# eib-64_center.net
KiCad netlist of a schematic drawn in EAGLE
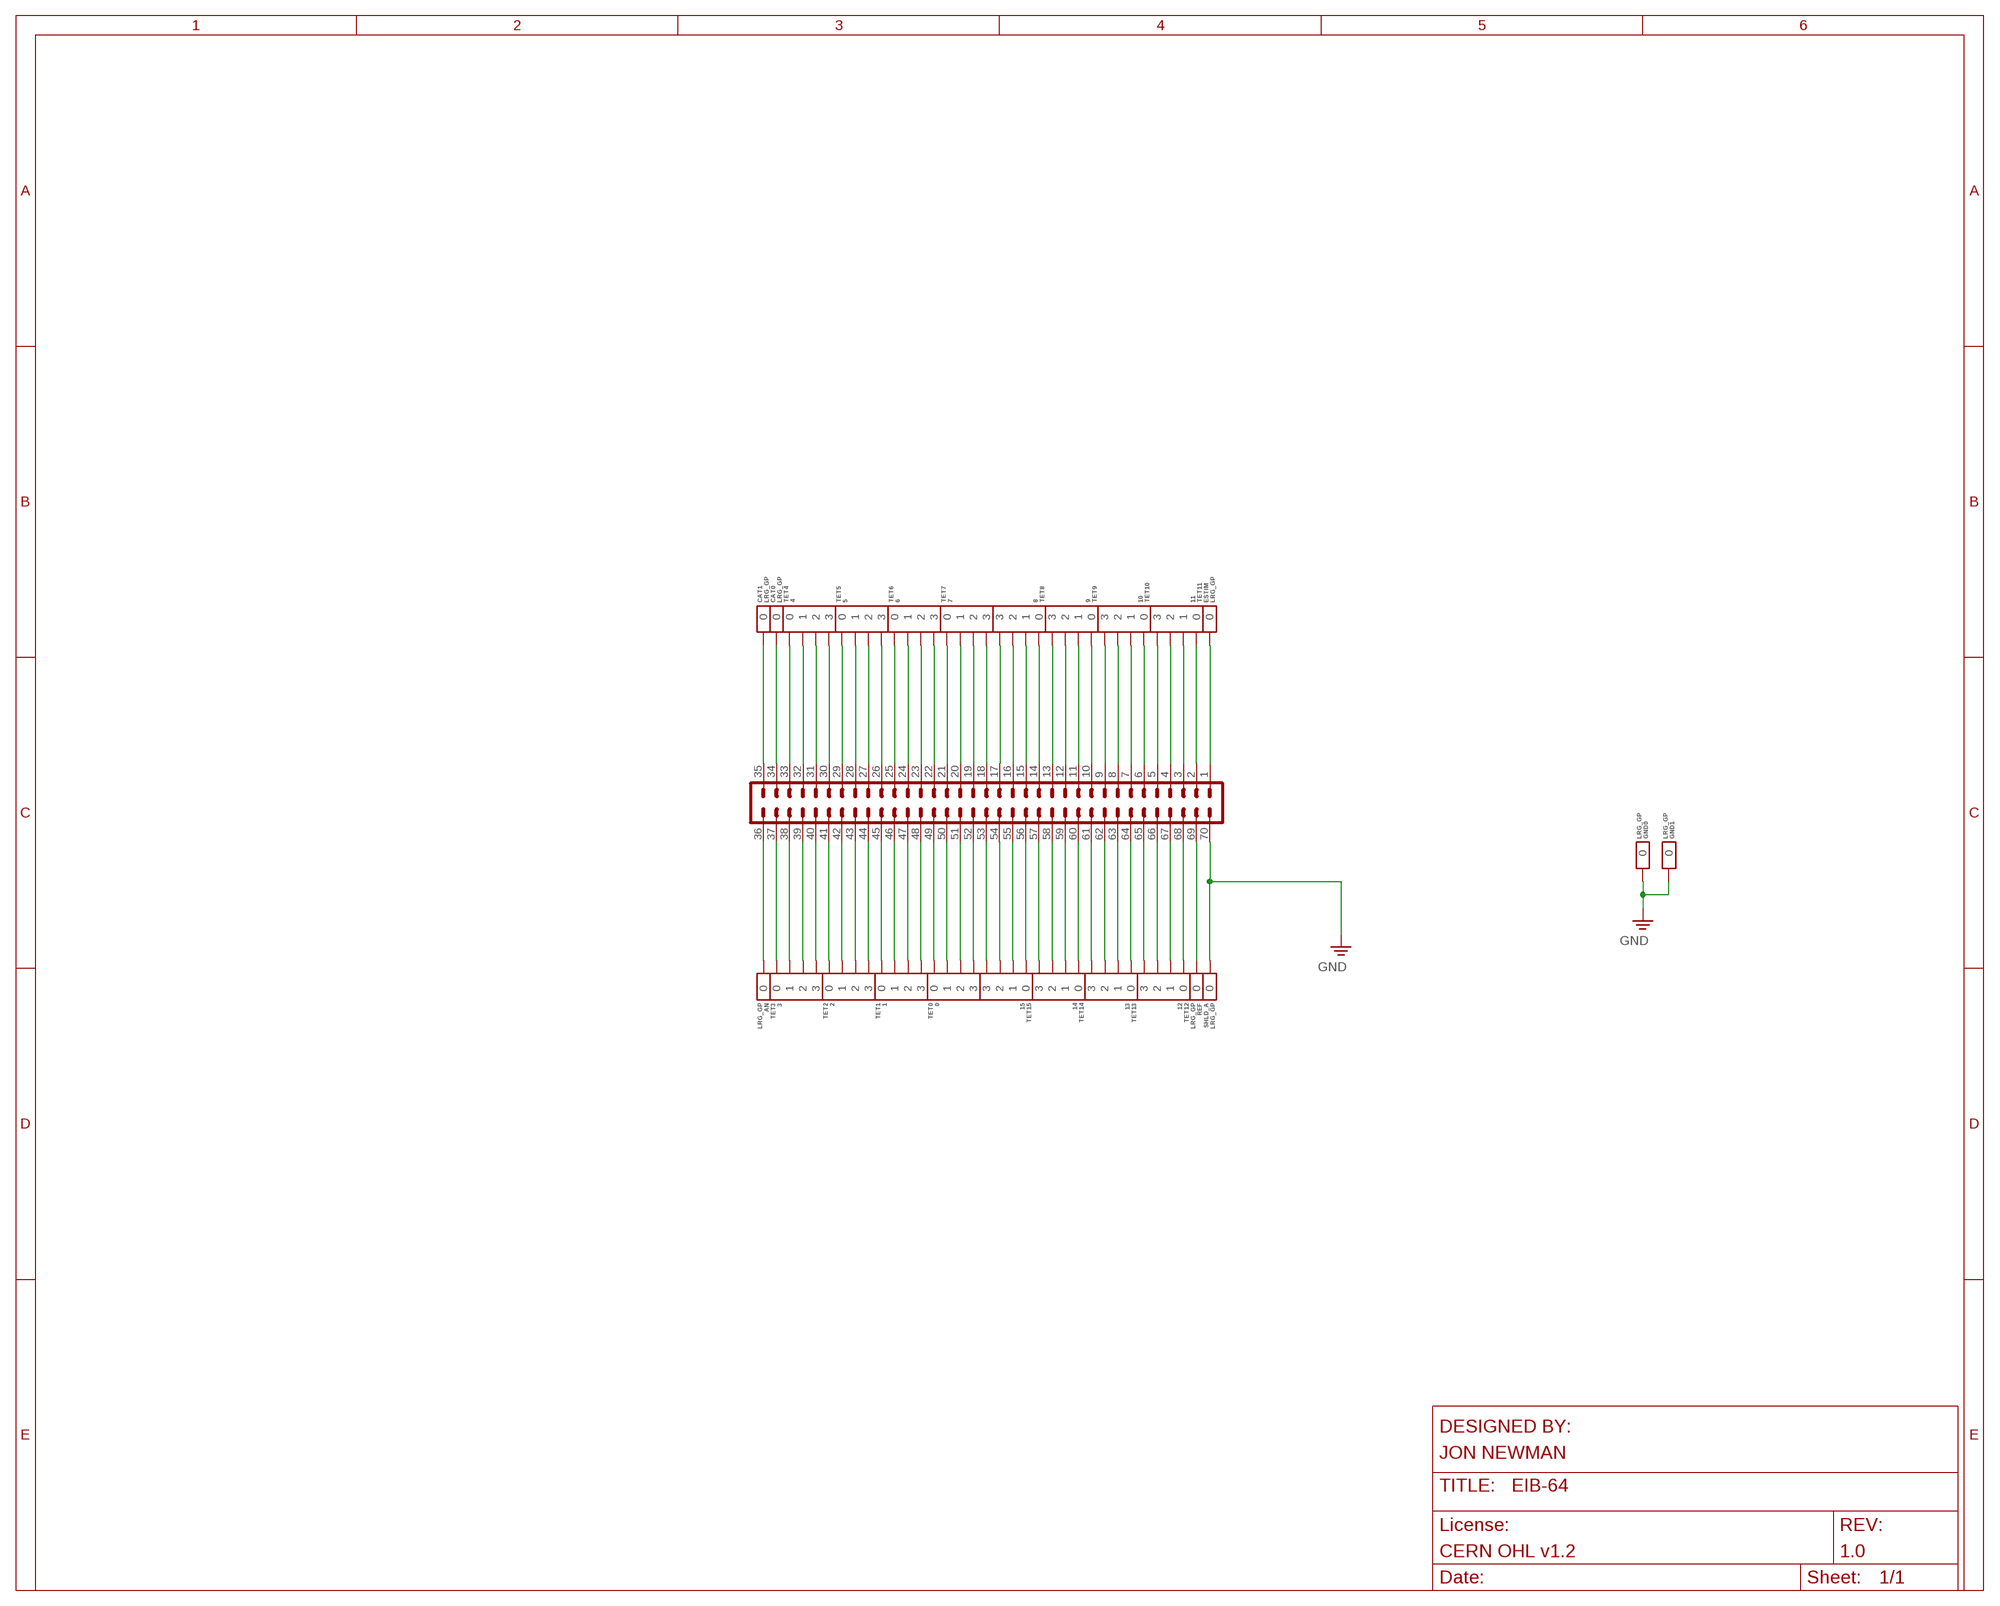
[diagram p0: schematic, sheet 1]

(export (version "E")
  (design (tool "Eeschema 10.0.6"))
  (components
    (comp (ref "AN")
      (value "LRG_GP")
      (footprint "eagle-import:GOLDPIN_0.5ID_0.7OD")
      (libsource (lib "eagle-import") (part "GOLDPIN_0.5ID_0.7OD"))
    )
    (comp (ref "CAT0")
      (value "LRG_GP")
      (footprint "eagle-import:GOLDPIN_0.5ID_0.7OD")
      (libsource (lib "eagle-import") (part "GOLDPIN_0.5ID_0.7OD"))
    )
    (comp (ref "CAT1")
      (value "LRG_GP")
      (footprint "eagle-import:GOLDPIN_0.5ID_0.7OD")
      (libsource (lib "eagle-import") (part "GOLDPIN_0.5ID_0.7OD"))
    )
    (comp (ref "ESTIM")
      (value "LRG_GP")
      (footprint "eagle-import:GOLDPIN_0.5ID_0.7OD")
      (libsource (lib "eagle-import") (part "GOLDPIN_0.5ID_0.7OD"))
    )
    (comp (ref "GND0")
      (value "LRG_GP")
      (footprint "eagle-import:GOLDPIN_0.5ID_0.7OD")
      (libsource (lib "eagle-import") (part "GOLDPIN_0.5ID_0.7OD"))
    )
    (comp (ref "GND1")
      (value "LRG_GP")
      (footprint "eagle-import:GOLDPIN_0.5ID_0.7OD")
      (libsource (lib "eagle-import") (part "GOLDPIN_0.5ID_0.7OD"))
    )
    (comp (ref "REF")
      (value "LRG_GP")
      (footprint "eagle-import:GOLDPIN_0.5ID_0.7OD")
      (libsource (lib "eagle-import") (part "GOLDPIN_0.5ID_0.7OD"))
    )
    (comp (ref "SHLD_A")
      (value "LRG_GP")
      (footprint "eagle-import:GOLDPIN_0.5ID_0.7OD")
      (libsource (lib "eagle-import") (part "GOLDPIN_0.5ID_0.7OD"))
    )
    (comp (ref "TET0")
      (value "0")
      (footprint "eagle-import:TETRODE_0.3ID_LINEAR_MOUSE")
      (libsource (lib "eagle-import") (part "TETRODE_0.3ID_LINEAR_MOUSE"))
    )
    (comp (ref "TET1")
      (value "1")
      (footprint "eagle-import:TETRODE_0.3ID_LINEAR_MOUSE")
      (libsource (lib "eagle-import") (part "TETRODE_0.3ID_LINEAR_MOUSE"))
    )
    (comp (ref "TET2")
      (value "2")
      (footprint "eagle-import:TETRODE_0.3ID_LINEAR_MOUSE")
      (libsource (lib "eagle-import") (part "TETRODE_0.3ID_LINEAR_MOUSE"))
    )
    (comp (ref "TET3")
      (value "3")
      (footprint "eagle-import:TETRODE_0.3ID_LINEAR_MOUSE")
      (libsource (lib "eagle-import") (part "TETRODE_0.3ID_LINEAR_MOUSE"))
    )
    (comp (ref "TET4")
      (value "4")
      (footprint "eagle-import:TETRODE_0.3ID_LINEAR_MOUSE")
      (libsource (lib "eagle-import") (part "TETRODE_0.3ID_LINEAR_MOUSE"))
    )
    (comp (ref "TET5")
      (value "5")
      (footprint "eagle-import:TETRODE_0.3ID_LINEAR_MOUSE")
      (libsource (lib "eagle-import") (part "TETRODE_0.3ID_LINEAR_MOUSE"))
    )
    (comp (ref "TET6")
      (value "6")
      (footprint "eagle-import:TETRODE_0.3ID_LINEAR_MOUSE")
      (libsource (lib "eagle-import") (part "TETRODE_0.3ID_LINEAR_MOUSE"))
    )
    (comp (ref "TET7")
      (value "7")
      (footprint "eagle-import:TETRODE_0.3ID_LINEAR_MOUSE")
      (libsource (lib "eagle-import") (part "TETRODE_0.3ID_LINEAR_MOUSE"))
    )
    (comp (ref "TET8")
      (value "8")
      (footprint "eagle-import:TETRODE_0.3ID_LINEAR_MOUSE")
      (libsource (lib "eagle-import") (part "TETRODE_0.3ID_LINEAR_MOUSE"))
    )
    (comp (ref "TET9")
      (value "9")
      (footprint "eagle-import:TETRODE_0.3ID_LINEAR_MOUSE")
      (libsource (lib "eagle-import") (part "TETRODE_0.3ID_LINEAR_MOUSE"))
    )
    (comp (ref "TET10")
      (value "10")
      (footprint "eagle-import:TETRODE_0.3ID_LINEAR_MOUSE")
      (libsource (lib "eagle-import") (part "TETRODE_0.3ID_LINEAR_MOUSE"))
    )
    (comp (ref "TET11")
      (value "11")
      (footprint "eagle-import:TETRODE_0.3ID_LINEAR_MOUSE")
      (libsource (lib "eagle-import") (part "TETRODE_0.3ID_LINEAR_MOUSE"))
    )
    (comp (ref "TET12")
      (value "12")
      (footprint "eagle-import:TETRODE_0.3ID_LINEAR_MOUSE")
      (libsource (lib "eagle-import") (part "TETRODE_0.3ID_LINEAR_MOUSE"))
    )
    (comp (ref "TET13")
      (value "13")
      (footprint "eagle-import:TETRODE_0.3ID_LINEAR_MOUSE")
      (libsource (lib "eagle-import") (part "TETRODE_0.3ID_LINEAR_MOUSE"))
    )
    (comp (ref "TET14")
      (value "14")
      (footprint "eagle-import:TETRODE_0.3ID_LINEAR_MOUSE")
      (libsource (lib "eagle-import") (part "TETRODE_0.3ID_LINEAR_MOUSE"))
    )
    (comp (ref "TET15")
      (value "15")
      (footprint "eagle-import:TETRODE_0.3ID_LINEAR_MOUSE")
      (libsource (lib "eagle-import") (part "TETRODE_0.3ID_LINEAR_MOUSE"))
    )
    (comp (ref "U$1")
      (value "PINHD-2X35_DF40REC")
      (footprint "eagle-import:DF40-70REC")
      (libsource (lib "eagle-import") (part "PINHD-2X35_DF40REC"))
    )
  )
  (nets
    (net (code "1") (name "GND") (class "Default")
      (node (ref "GND0") (pin "P$1") (pinfunction "0_P$1") (pintype "bidirectional"))
      (node (ref "GND1") (pin "P$1") (pinfunction "0_P$1") (pintype "bidirectional"))
      (node (ref "SHLD_A") (pin "P$1") (pinfunction "0_P$1") (pintype "bidirectional"))
      (node (ref "U$1") (pin "70") (pinfunction "70_70") (pintype "bidirectional"))
    )
    (net (code "2") (name "Net-(AN-0)") (class "Default")
      (node (ref "AN") (pin "P$1") (pinfunction "0_P$1") (pintype "bidirectional"))
      (node (ref "U$1") (pin "36") (pinfunction "36_36") (pintype "bidirectional"))
    )
    (net (code "3") (name "Net-(CAT0-0)") (class "Default")
      (node (ref "CAT0") (pin "P$1") (pinfunction "0_P$1") (pintype "bidirectional"))
      (node (ref "U$1") (pin "34") (pinfunction "34_34") (pintype "bidirectional"))
    )
    (net (code "4") (name "Net-(CAT1-0)") (class "Default")
      (node (ref "CAT1") (pin "P$1") (pinfunction "0_P$1") (pintype "bidirectional"))
      (node (ref "U$1") (pin "35") (pinfunction "35_35") (pintype "bidirectional"))
    )
    (net (code "5") (name "Net-(ESTIM-0)") (class "Default")
      (node (ref "ESTIM") (pin "P$1") (pinfunction "0_P$1") (pintype "bidirectional"))
      (node (ref "U$1") (pin "1") (pinfunction "1_1") (pintype "bidirectional"))
    )
    (net (code "6") (name "Net-(REF-0)") (class "Default")
      (node (ref "REF") (pin "P$1") (pinfunction "0_P$1") (pintype "bidirectional"))
      (node (ref "U$1") (pin "69") (pinfunction "69_69") (pintype "bidirectional"))
    )
    (net (code "7") (name "Net-(TET0-Pad0)") (class "Default")
      (node (ref "TET0") (pin "0") (pinfunction "0_0") (pintype "bidirectional"))
      (node (ref "U$1") (pin "49") (pinfunction "49_49") (pintype "bidirectional"))
    )
    (net (code "8") (name "Net-(TET0-Pad1)") (class "Default")
      (node (ref "TET0") (pin "1") (pinfunction "1_1") (pintype "bidirectional"))
      (node (ref "U$1") (pin "50") (pinfunction "50_50") (pintype "bidirectional"))
    )
    (net (code "9") (name "Net-(TET0-Pad2)") (class "Default")
      (node (ref "TET0") (pin "2") (pinfunction "2_2") (pintype "bidirectional"))
      (node (ref "U$1") (pin "51") (pinfunction "51_51") (pintype "bidirectional"))
    )
    (net (code "10") (name "Net-(TET0-Pad3)") (class "Default")
      (node (ref "TET0") (pin "3") (pinfunction "3_3") (pintype "bidirectional"))
      (node (ref "U$1") (pin "52") (pinfunction "52_52") (pintype "bidirectional"))
    )
    (net (code "11") (name "Net-(TET1-Pad0)") (class "Default")
      (node (ref "TET1") (pin "0") (pinfunction "0_0") (pintype "bidirectional"))
      (node (ref "U$1") (pin "45") (pinfunction "45_45") (pintype "bidirectional"))
    )
    (net (code "12") (name "Net-(TET1-Pad1)") (class "Default")
      (node (ref "TET1") (pin "1") (pinfunction "1_1") (pintype "bidirectional"))
      (node (ref "U$1") (pin "46") (pinfunction "46_46") (pintype "bidirectional"))
    )
    (net (code "13") (name "Net-(TET1-Pad2)") (class "Default")
      (node (ref "TET1") (pin "2") (pinfunction "2_2") (pintype "bidirectional"))
      (node (ref "U$1") (pin "47") (pinfunction "47_47") (pintype "bidirectional"))
    )
    (net (code "14") (name "Net-(TET1-Pad3)") (class "Default")
      (node (ref "TET1") (pin "3") (pinfunction "3_3") (pintype "bidirectional"))
      (node (ref "U$1") (pin "48") (pinfunction "48_48") (pintype "bidirectional"))
    )
    (net (code "15") (name "Net-(TET2-Pad0)") (class "Default")
      (node (ref "TET2") (pin "0") (pinfunction "0_0") (pintype "bidirectional"))
      (node (ref "U$1") (pin "41") (pinfunction "41_41") (pintype "bidirectional"))
    )
    (net (code "16") (name "Net-(TET2-Pad1)") (class "Default")
      (node (ref "TET2") (pin "1") (pinfunction "1_1") (pintype "bidirectional"))
      (node (ref "U$1") (pin "42") (pinfunction "42_42") (pintype "bidirectional"))
    )
    (net (code "17") (name "Net-(TET2-Pad2)") (class "Default")
      (node (ref "TET2") (pin "2") (pinfunction "2_2") (pintype "bidirectional"))
      (node (ref "U$1") (pin "43") (pinfunction "43_43") (pintype "bidirectional"))
    )
    (net (code "18") (name "Net-(TET2-Pad3)") (class "Default")
      (node (ref "TET2") (pin "3") (pinfunction "3_3") (pintype "bidirectional"))
      (node (ref "U$1") (pin "44") (pinfunction "44_44") (pintype "bidirectional"))
    )
    (net (code "19") (name "Net-(TET3-Pad0)") (class "Default")
      (node (ref "TET3") (pin "0") (pinfunction "0_0") (pintype "bidirectional"))
      (node (ref "U$1") (pin "37") (pinfunction "37_37") (pintype "bidirectional"))
    )
    (net (code "20") (name "Net-(TET3-Pad1)") (class "Default")
      (node (ref "TET3") (pin "1") (pinfunction "1_1") (pintype "bidirectional"))
      (node (ref "U$1") (pin "38") (pinfunction "38_38") (pintype "bidirectional"))
    )
    (net (code "21") (name "Net-(TET3-Pad2)") (class "Default")
      (node (ref "TET3") (pin "2") (pinfunction "2_2") (pintype "bidirectional"))
      (node (ref "U$1") (pin "39") (pinfunction "39_39") (pintype "bidirectional"))
    )
    (net (code "22") (name "Net-(TET3-Pad3)") (class "Default")
      (node (ref "TET3") (pin "3") (pinfunction "3_3") (pintype "bidirectional"))
      (node (ref "U$1") (pin "40") (pinfunction "40_40") (pintype "bidirectional"))
    )
    (net (code "23") (name "Net-(TET4-Pad0)") (class "Default")
      (node (ref "TET4") (pin "0") (pinfunction "0_0") (pintype "bidirectional"))
      (node (ref "U$1") (pin "33") (pinfunction "33_33") (pintype "bidirectional"))
    )
    (net (code "24") (name "Net-(TET4-Pad1)") (class "Default")
      (node (ref "TET4") (pin "1") (pinfunction "1_1") (pintype "bidirectional"))
      (node (ref "U$1") (pin "32") (pinfunction "32_32") (pintype "bidirectional"))
    )
    (net (code "25") (name "Net-(TET4-Pad2)") (class "Default")
      (node (ref "TET4") (pin "2") (pinfunction "2_2") (pintype "bidirectional"))
      (node (ref "U$1") (pin "31") (pinfunction "31_31") (pintype "bidirectional"))
    )
    (net (code "26") (name "Net-(TET4-Pad3)") (class "Default")
      (node (ref "TET4") (pin "3") (pinfunction "3_3") (pintype "bidirectional"))
      (node (ref "U$1") (pin "30") (pinfunction "30_30") (pintype "bidirectional"))
    )
    (net (code "27") (name "Net-(TET5-Pad0)") (class "Default")
      (node (ref "TET5") (pin "0") (pinfunction "0_0") (pintype "bidirectional"))
      (node (ref "U$1") (pin "29") (pinfunction "29_29") (pintype "bidirectional"))
    )
    (net (code "28") (name "Net-(TET5-Pad1)") (class "Default")
      (node (ref "TET5") (pin "1") (pinfunction "1_1") (pintype "bidirectional"))
      (node (ref "U$1") (pin "28") (pinfunction "28_28") (pintype "bidirectional"))
    )
    (net (code "29") (name "Net-(TET5-Pad2)") (class "Default")
      (node (ref "TET5") (pin "2") (pinfunction "2_2") (pintype "bidirectional"))
      (node (ref "U$1") (pin "27") (pinfunction "27_27") (pintype "bidirectional"))
    )
    (net (code "30") (name "Net-(TET5-Pad3)") (class "Default")
      (node (ref "TET5") (pin "3") (pinfunction "3_3") (pintype "bidirectional"))
      (node (ref "U$1") (pin "26") (pinfunction "26_26") (pintype "bidirectional"))
    )
    (net (code "31") (name "Net-(TET6-Pad0)") (class "Default")
      (node (ref "TET6") (pin "0") (pinfunction "0_0") (pintype "bidirectional"))
      (node (ref "U$1") (pin "25") (pinfunction "25_25") (pintype "bidirectional"))
    )
    (net (code "32") (name "Net-(TET6-Pad1)") (class "Default")
      (node (ref "TET6") (pin "1") (pinfunction "1_1") (pintype "bidirectional"))
      (node (ref "U$1") (pin "24") (pinfunction "24_24") (pintype "bidirectional"))
    )
    (net (code "33") (name "Net-(TET6-Pad2)") (class "Default")
      (node (ref "TET6") (pin "2") (pinfunction "2_2") (pintype "bidirectional"))
      (node (ref "U$1") (pin "23") (pinfunction "23_23") (pintype "bidirectional"))
    )
    (net (code "34") (name "Net-(TET6-Pad3)") (class "Default")
      (node (ref "TET6") (pin "3") (pinfunction "3_3") (pintype "bidirectional"))
      (node (ref "U$1") (pin "22") (pinfunction "22_22") (pintype "bidirectional"))
    )
    (net (code "35") (name "Net-(TET7-Pad0)") (class "Default")
      (node (ref "TET7") (pin "0") (pinfunction "0_0") (pintype "bidirectional"))
      (node (ref "U$1") (pin "21") (pinfunction "21_21") (pintype "bidirectional"))
    )
    (net (code "36") (name "Net-(TET7-Pad1)") (class "Default")
      (node (ref "TET7") (pin "1") (pinfunction "1_1") (pintype "bidirectional"))
      (node (ref "U$1") (pin "20") (pinfunction "20_20") (pintype "bidirectional"))
    )
    (net (code "37") (name "Net-(TET7-Pad2)") (class "Default")
      (node (ref "TET7") (pin "2") (pinfunction "2_2") (pintype "bidirectional"))
      (node (ref "U$1") (pin "19") (pinfunction "19_19") (pintype "bidirectional"))
    )
    (net (code "38") (name "Net-(TET7-Pad3)") (class "Default")
      (node (ref "TET7") (pin "3") (pinfunction "3_3") (pintype "bidirectional"))
      (node (ref "U$1") (pin "18") (pinfunction "18_18") (pintype "bidirectional"))
    )
    (net (code "39") (name "Net-(TET8-Pad0)") (class "Default")
      (node (ref "TET8") (pin "0") (pinfunction "0_0") (pintype "bidirectional"))
      (node (ref "U$1") (pin "14") (pinfunction "14_14") (pintype "bidirectional"))
    )
    (net (code "40") (name "Net-(TET8-Pad1)") (class "Default")
      (node (ref "TET8") (pin "1") (pinfunction "1_1") (pintype "bidirectional"))
      (node (ref "U$1") (pin "15") (pinfunction "15_15") (pintype "bidirectional"))
    )
    (net (code "41") (name "Net-(TET8-Pad2)") (class "Default")
      (node (ref "TET8") (pin "2") (pinfunction "2_2") (pintype "bidirectional"))
      (node (ref "U$1") (pin "16") (pinfunction "16_16") (pintype "bidirectional"))
    )
    (net (code "42") (name "Net-(TET8-Pad3)") (class "Default")
      (node (ref "TET8") (pin "3") (pinfunction "3_3") (pintype "bidirectional"))
      (node (ref "U$1") (pin "17") (pinfunction "17_17") (pintype "bidirectional"))
    )
    (net (code "43") (name "Net-(TET9-Pad0)") (class "Default")
      (node (ref "TET9") (pin "0") (pinfunction "0_0") (pintype "bidirectional"))
      (node (ref "U$1") (pin "10") (pinfunction "10_10") (pintype "bidirectional"))
    )
    (net (code "44") (name "Net-(TET9-Pad1)") (class "Default")
      (node (ref "TET9") (pin "1") (pinfunction "1_1") (pintype "bidirectional"))
      (node (ref "U$1") (pin "11") (pinfunction "11_11") (pintype "bidirectional"))
    )
    (net (code "45") (name "Net-(TET9-Pad2)") (class "Default")
      (node (ref "TET9") (pin "2") (pinfunction "2_2") (pintype "bidirectional"))
      (node (ref "U$1") (pin "12") (pinfunction "12_12") (pintype "bidirectional"))
    )
    (net (code "46") (name "Net-(TET9-Pad3)") (class "Default")
      (node (ref "TET9") (pin "3") (pinfunction "3_3") (pintype "bidirectional"))
      (node (ref "U$1") (pin "13") (pinfunction "13_13") (pintype "bidirectional"))
    )
    (net (code "47") (name "Net-(TET10-Pad0)") (class "Default")
      (node (ref "TET10") (pin "0") (pinfunction "0_0") (pintype "bidirectional"))
      (node (ref "U$1") (pin "6") (pinfunction "6_6") (pintype "bidirectional"))
    )
    (net (code "48") (name "Net-(TET10-Pad1)") (class "Default")
      (node (ref "TET10") (pin "1") (pinfunction "1_1") (pintype "bidirectional"))
      (node (ref "U$1") (pin "7") (pinfunction "7_7") (pintype "bidirectional"))
    )
    (net (code "49") (name "Net-(TET10-Pad2)") (class "Default")
      (node (ref "TET10") (pin "2") (pinfunction "2_2") (pintype "bidirectional"))
      (node (ref "U$1") (pin "8") (pinfunction "8_8") (pintype "bidirectional"))
    )
    (net (code "50") (name "Net-(TET10-Pad3)") (class "Default")
      (node (ref "TET10") (pin "3") (pinfunction "3_3") (pintype "bidirectional"))
      (node (ref "U$1") (pin "9") (pinfunction "9_9") (pintype "bidirectional"))
    )
    (net (code "51") (name "Net-(TET11-Pad0)") (class "Default")
      (node (ref "TET11") (pin "0") (pinfunction "0_0") (pintype "bidirectional"))
      (node (ref "U$1") (pin "2") (pinfunction "2_2") (pintype "bidirectional"))
    )
    (net (code "52") (name "Net-(TET11-Pad1)") (class "Default")
      (node (ref "TET11") (pin "1") (pinfunction "1_1") (pintype "bidirectional"))
      (node (ref "U$1") (pin "3") (pinfunction "3_3") (pintype "bidirectional"))
    )
    (net (code "53") (name "Net-(TET11-Pad2)") (class "Default")
      (node (ref "TET11") (pin "2") (pinfunction "2_2") (pintype "bidirectional"))
      (node (ref "U$1") (pin "4") (pinfunction "4_4") (pintype "bidirectional"))
    )
    (net (code "54") (name "Net-(TET11-Pad3)") (class "Default")
      (node (ref "TET11") (pin "3") (pinfunction "3_3") (pintype "bidirectional"))
      (node (ref "U$1") (pin "5") (pinfunction "5_5") (pintype "bidirectional"))
    )
    (net (code "55") (name "Net-(TET12-Pad0)") (class "Default")
      (node (ref "TET12") (pin "0") (pinfunction "0_0") (pintype "bidirectional"))
      (node (ref "U$1") (pin "68") (pinfunction "68_68") (pintype "bidirectional"))
    )
    (net (code "56") (name "Net-(TET12-Pad1)") (class "Default")
      (node (ref "TET12") (pin "1") (pinfunction "1_1") (pintype "bidirectional"))
      (node (ref "U$1") (pin "67") (pinfunction "67_67") (pintype "bidirectional"))
    )
    (net (code "57") (name "Net-(TET12-Pad2)") (class "Default")
      (node (ref "TET12") (pin "2") (pinfunction "2_2") (pintype "bidirectional"))
      (node (ref "U$1") (pin "66") (pinfunction "66_66") (pintype "bidirectional"))
    )
    (net (code "58") (name "Net-(TET12-Pad3)") (class "Default")
      (node (ref "TET12") (pin "3") (pinfunction "3_3") (pintype "bidirectional"))
      (node (ref "U$1") (pin "65") (pinfunction "65_65") (pintype "bidirectional"))
    )
    (net (code "59") (name "Net-(TET13-Pad0)") (class "Default")
      (node (ref "TET13") (pin "0") (pinfunction "0_0") (pintype "bidirectional"))
      (node (ref "U$1") (pin "64") (pinfunction "64_64") (pintype "bidirectional"))
    )
    (net (code "60") (name "Net-(TET13-Pad1)") (class "Default")
      (node (ref "TET13") (pin "1") (pinfunction "1_1") (pintype "bidirectional"))
      (node (ref "U$1") (pin "63") (pinfunction "63_63") (pintype "bidirectional"))
    )
    (net (code "61") (name "Net-(TET13-Pad2)") (class "Default")
      (node (ref "TET13") (pin "2") (pinfunction "2_2") (pintype "bidirectional"))
      (node (ref "U$1") (pin "62") (pinfunction "62_62") (pintype "bidirectional"))
    )
    (net (code "62") (name "Net-(TET13-Pad3)") (class "Default")
      (node (ref "TET13") (pin "3") (pinfunction "3_3") (pintype "bidirectional"))
      (node (ref "U$1") (pin "61") (pinfunction "61_61") (pintype "bidirectional"))
    )
    (net (code "63") (name "Net-(TET14-Pad0)") (class "Default")
      (node (ref "TET14") (pin "0") (pinfunction "0_0") (pintype "bidirectional"))
      (node (ref "U$1") (pin "60") (pinfunction "60_60") (pintype "bidirectional"))
    )
    (net (code "64") (name "Net-(TET14-Pad1)") (class "Default")
      (node (ref "TET14") (pin "1") (pinfunction "1_1") (pintype "bidirectional"))
      (node (ref "U$1") (pin "59") (pinfunction "59_59") (pintype "bidirectional"))
    )
    (net (code "65") (name "Net-(TET14-Pad2)") (class "Default")
      (node (ref "TET14") (pin "2") (pinfunction "2_2") (pintype "bidirectional"))
      (node (ref "U$1") (pin "58") (pinfunction "58_58") (pintype "bidirectional"))
    )
    (net (code "66") (name "Net-(TET14-Pad3)") (class "Default")
      (node (ref "TET14") (pin "3") (pinfunction "3_3") (pintype "bidirectional"))
      (node (ref "U$1") (pin "57") (pinfunction "57_57") (pintype "bidirectional"))
    )
    (net (code "67") (name "Net-(TET15-Pad0)") (class "Default")
      (node (ref "TET15") (pin "0") (pinfunction "0_0") (pintype "bidirectional"))
      (node (ref "U$1") (pin "56") (pinfunction "56_56") (pintype "bidirectional"))
    )
    (net (code "68") (name "Net-(TET15-Pad1)") (class "Default")
      (node (ref "TET15") (pin "1") (pinfunction "1_1") (pintype "bidirectional"))
      (node (ref "U$1") (pin "55") (pinfunction "55_55") (pintype "bidirectional"))
    )
    (net (code "69") (name "Net-(TET15-Pad2)") (class "Default")
      (node (ref "TET15") (pin "2") (pinfunction "2_2") (pintype "bidirectional"))
      (node (ref "U$1") (pin "54") (pinfunction "54_54") (pintype "bidirectional"))
    )
    (net (code "70") (name "Net-(TET15-Pad3)") (class "Default")
      (node (ref "TET15") (pin "3") (pinfunction "3_3") (pintype "bidirectional"))
      (node (ref "U$1") (pin "53") (pinfunction "53_53") (pintype "bidirectional"))
    )
  )
)
